# Sensors.net
KiCad netlist of a schematic drawn in Altium Designer
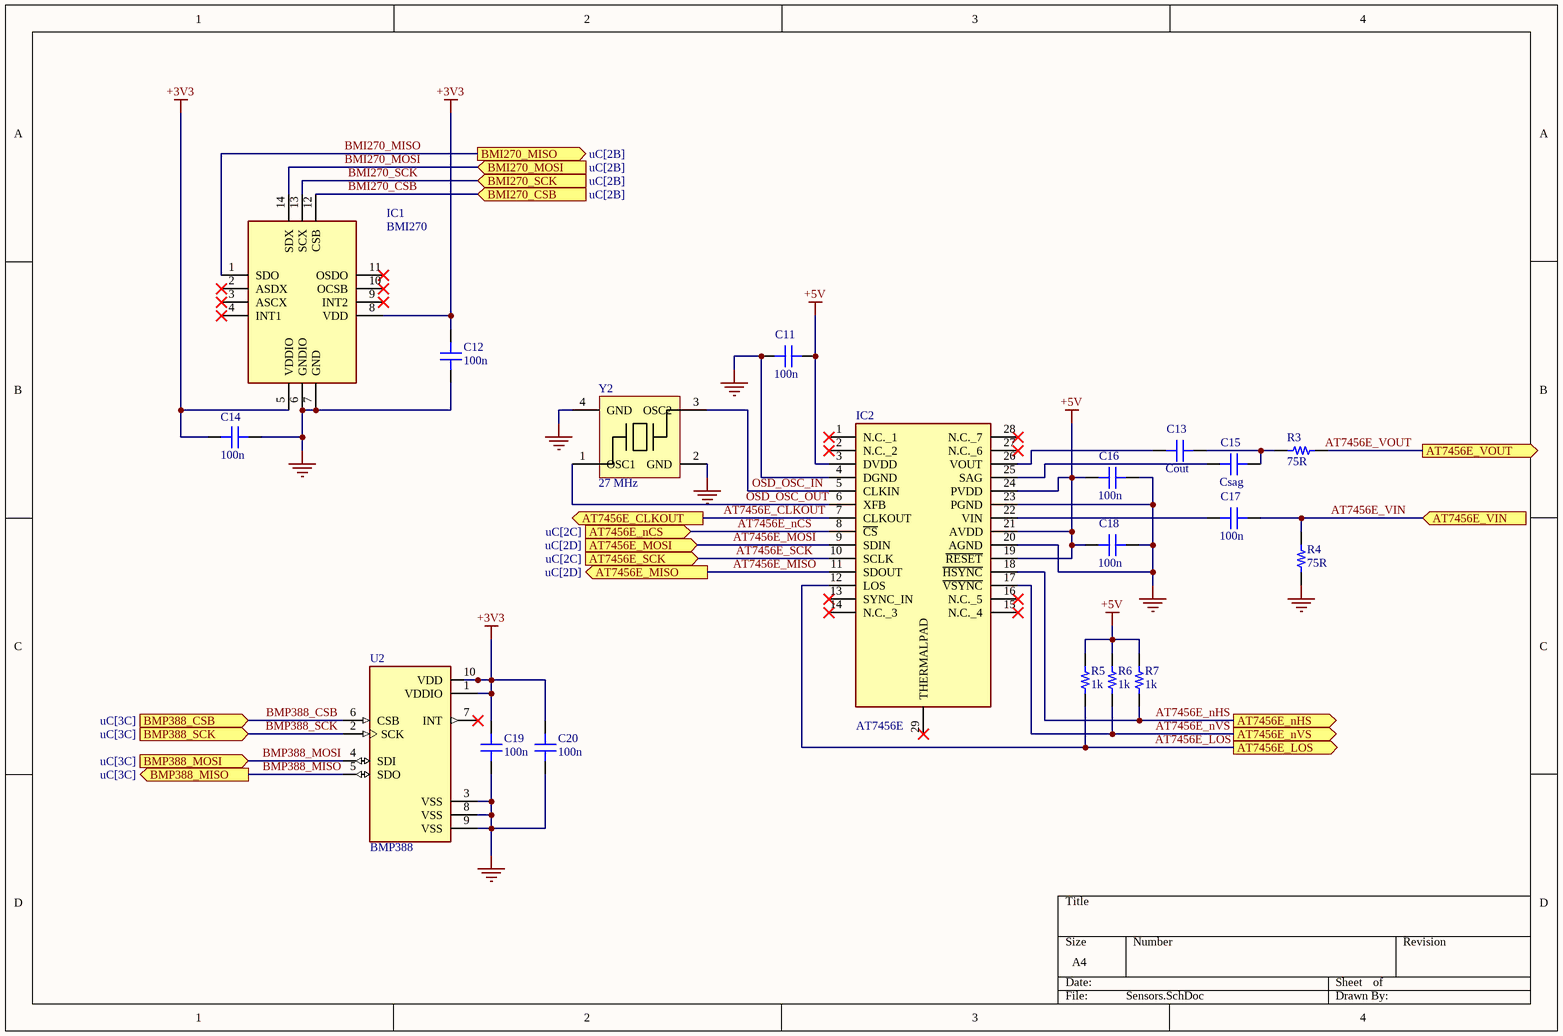
[diagram p0: Sensors.SchDoc]

(export (version "E")
  (design (tool "Eeschema 10.0.6"))
  (components
    (comp (ref "C11")
      (value "0.1 µF")
      (footprint "CAP 0603_1608")
      (description "CAP CER 0.1UF 50V X7R 0603")
      (fields
        (field (name "PART NUMBER") "CL10B104KB8NNNC")
        (field (name "CAPACITANCE") "100n")
        (field (name "MANUFACTURER") "Samsung Electro-Mechanics")
      )
      (libsource (lib "Celestial Altium Library - altium_library") (part "Capacitor"))
    )
    (comp (ref "C12")
      (value "0.1 µF")
      (footprint "CAP 0603_1608")
      (description "CAP CER 0.1UF 50V X7R 0603")
      (fields
        (field (name "PART NUMBER") "CL10B104KB8NNNC")
        (field (name "CAPACITANCE") "100n")
        (field (name "MANUFACTURER") "Samsung Electro-Mechanics")
      )
      (libsource (lib "Celestial Altium Library - altium_library") (part "Capacitor"))
    )
    (comp (ref "C13")
      (value "0.1 µF")
      (footprint "CAP 0603_1608")
      (description "CAP CER 0.1UF 50V X7R 0603")
      (fields
        (field (name "PART NUMBER") "CL10B104KB8NNNC")
        (field (name "CAPACITANCE") "Cout")
        (field (name "MANUFACTURER") "Samsung Electro-Mechanics")
      )
      (libsource (lib "Celestial Altium Library - altium_library") (part "Capacitor"))
    )
    (comp (ref "C14")
      (value "0.1 µF")
      (footprint "CAP 0603_1608")
      (description "CAP CER 0.1UF 50V X7R 0603")
      (fields
        (field (name "PART NUMBER") "CL10B104KB8NNNC")
        (field (name "CAPACITANCE") "100n")
        (field (name "MANUFACTURER") "Samsung Electro-Mechanics")
      )
      (libsource (lib "Celestial Altium Library - altium_library") (part "Capacitor"))
    )
    (comp (ref "C15")
      (value "0.1 µF")
      (footprint "CAP 0603_1608")
      (description "CAP CER 0.1UF 50V X7R 0603")
      (fields
        (field (name "PART NUMBER") "CL10B104KB8NNNC")
        (field (name "CAPACITANCE") "Csag")
        (field (name "MANUFACTURER") "Samsung Electro-Mechanics")
      )
      (libsource (lib "Celestial Altium Library - altium_library") (part "Capacitor"))
    )
    (comp (ref "C16")
      (value "0.1 µF")
      (footprint "CAP 0603_1608")
      (description "CAP CER 0.1UF 50V X7R 0603")
      (fields
        (field (name "PART NUMBER") "CL10B104KB8NNNC")
        (field (name "CAPACITANCE") "100n")
        (field (name "MANUFACTURER") "Samsung Electro-Mechanics")
      )
      (libsource (lib "Celestial Altium Library - altium_library") (part "Capacitor"))
    )
    (comp (ref "C17")
      (value "0.1 µF")
      (footprint "CAP 0603_1608")
      (description "CAP CER 0.1UF 50V X7R 0603")
      (fields
        (field (name "PART NUMBER") "CL10B104KB8NNNC")
        (field (name "CAPACITANCE") "100n")
        (field (name "MANUFACTURER") "Samsung Electro-Mechanics")
      )
      (libsource (lib "Celestial Altium Library - altium_library") (part "Capacitor"))
    )
    (comp (ref "C18")
      (value "0.1 µF")
      (footprint "CAP 0603_1608")
      (description "CAP CER 0.1UF 50V X7R 0603")
      (fields
        (field (name "PART NUMBER") "CL10B104KB8NNNC")
        (field (name "CAPACITANCE") "100n")
        (field (name "MANUFACTURER") "Samsung Electro-Mechanics")
      )
      (libsource (lib "Celestial Altium Library - altium_library") (part "Capacitor"))
    )
    (comp (ref "C19")
      (value "0.1 µF")
      (footprint "CAP 0603_1608")
      (description "CAP CER 0.1UF 50V X7R 0603")
      (fields
        (field (name "PART NUMBER") "CL10B104KB8NNNC")
        (field (name "CAPACITANCE") "100n")
        (field (name "MANUFACTURER") "Samsung Electro-Mechanics")
      )
      (libsource (lib "Celestial Altium Library - altium_library") (part "Capacitor"))
    )
    (comp (ref "C20")
      (value "0.1 µF")
      (footprint "CAP 0603_1608")
      (description "CAP CER 0.1UF 50V X7R 0603")
      (fields
        (field (name "PART NUMBER") "CL10B104KB8NNNC")
        (field (name "CAPACITANCE") "100n")
        (field (name "MANUFACTURER") "Samsung Electro-Mechanics")
      )
      (libsource (lib "Celestial Altium Library - altium_library") (part "Capacitor"))
    )
    (comp (ref "IC1")
      (value "BMI270")
      (footprint "SamacSys:BMI270")
      (description "Integrated Circuit")
      (fields (field (name "MOUSER PART NUMBER") "262-BMI270"))
      (libsource (lib "*") (part "BMI270"))
    )
    (comp (ref "IC2")
      (value "AT7456E")
      (footprint "SamacSys:SOP65P640X120-29N")
      (description "Integrated Circuit")
      (libsource (lib "SamacSys") (part "AT7456E"))
    )
    (comp (ref "R3")
      (value "75R")
      (footprint "YAGEO RES 0603_1608")
      (description "RES 75 OHM 1% 1/10W 0603")
      (fields (field (name "PART NUMBER") "RC0603FR-0775RL") (field (name "MANUFACTURER") "Yageo"))
      (libsource (lib "Celestial Altium Library - altium_library") (part "Resistor"))
    )
    (comp (ref "R4")
      (value "75R")
      (footprint "YAGEO RES 0603_1608")
      (description "RES 75 OHM 1% 1/10W 0603")
      (fields (field (name "PART NUMBER") "RC0603FR-0775RL") (field (name "MANUFACTURER") "Yageo"))
      (libsource (lib "Celestial Altium Library - altium_library") (part "Resistor"))
    )
    (comp (ref "R5")
      (value "1k")
      (footprint "YAGEO RES 0603_1608")
      (description "RES 1K OHM 1% 1/10W 0603")
      (fields (field (name "PART NUMBER") "RC0603FR-071KL") (field (name "MANUFACTURER") "Yageo"))
      (libsource (lib "Celestial Altium Library - altium_library") (part "Resistor"))
    )
    (comp (ref "R6")
      (value "1k")
      (footprint "YAGEO RES 0603_1608")
      (description "RES 1K OHM 1% 1/10W 0603")
      (fields (field (name "PART NUMBER") "RC0603FR-071KL") (field (name "MANUFACTURER") "Yageo"))
      (libsource (lib "Celestial Altium Library - altium_library") (part "Resistor"))
    )
    (comp (ref "R7")
      (value "1k")
      (footprint "YAGEO RES 0603_1608")
      (description "RES 1K OHM 1% 1/10W 0603")
      (fields (field (name "PART NUMBER") "RC0603FR-071KL") (field (name "MANUFACTURER") "Yageo"))
      (libsource (lib "Celestial Altium Library - altium_library") (part "Resistor"))
    )
    (comp (ref "U2")
      (value "BMP388")
      (footprint "PQFN50P200X200X80-10N")
      (description "P-Sensor SPI I2C 1, 25 Bar SMD")
      (libsource (lib "BMP388") (part "BMP388"))
    )
    (comp (ref "Y2")
      (value "27 MHz")
      (footprint "X322527MSB4SI")
      (libsource (lib "SamacSys") (part "X322527MSB4SI"))
    )
  )
  (nets
    (net (code "1") (name "+3V3") (class "Default")
      (node (ref "C12") (pin "1") (pinfunction "1_1") (pintype "passive"))
      (node (ref "C14") (pin "2") (pinfunction "2_2") (pintype "passive"))
      (node (ref "C19") (pin "1") (pinfunction "1_1") (pintype "passive"))
      (node (ref "C20") (pin "1") (pinfunction "1_1") (pintype "passive"))
      (node (ref "IC1") (pin "5") (pinfunction "VDDIO_5") (pintype "passive"))
      (node (ref "IC1") (pin "8") (pinfunction "VDD_8") (pintype "passive"))
      (node (ref "U2") (pin "1") (pinfunction "VDDIO_1") (pintype "power_in"))
      (node (ref "U2") (pin "10") (pinfunction "VDD_10") (pintype "power_in"))
    )
    (net (code "2") (name "+5V") (class "Default")
      (node (ref "C11") (pin "2") (pinfunction "2_2") (pintype "passive"))
      (node (ref "C16") (pin "1") (pinfunction "1_1") (pintype "passive"))
      (node (ref "C18") (pin "1") (pinfunction "1_1") (pintype "passive"))
      (node (ref "IC2") (pin "19") (pinfunction "~{RESET}_19") (pintype "passive"))
      (node (ref "IC2") (pin "21") (pinfunction "AVDD_21") (pintype "passive"))
      (node (ref "IC2") (pin "24") (pinfunction "PVDD_24") (pintype "passive"))
      (node (ref "IC2") (pin "3") (pinfunction "DVDD_3") (pintype "passive"))
      (node (ref "R5") (pin "2") (pinfunction "2_2") (pintype "passive"))
      (node (ref "R6") (pin "2") (pinfunction "2_2") (pintype "passive"))
      (node (ref "R7") (pin "2") (pinfunction "2_2") (pintype "passive"))
    )
    (net (code "3") (name "/AT7456E_CLKOUT") (class "Default")
      (node (ref "IC2") (pin "7") (pinfunction "CLKOUT_7") (pintype "passive"))
    )
    (net (code "4") (name "/AT7456E_LOS") (class "Default")
      (node (ref "IC2") (pin "12") (pinfunction "LOS_12") (pintype "passive"))
      (node (ref "R5") (pin "1") (pinfunction "1_1") (pintype "passive"))
    )
    (net (code "5") (name "/AT7456E_MISO") (class "Default")
      (node (ref "IC2") (pin "11") (pinfunction "SDOUT_11") (pintype "passive"))
    )
    (net (code "6") (name "/AT7456E_MOSI") (class "Default")
      (node (ref "IC2") (pin "9") (pinfunction "SDIN_9") (pintype "passive"))
    )
    (net (code "7") (name "/AT7456E_SCK") (class "Default")
      (node (ref "IC2") (pin "10") (pinfunction "SCLK_10") (pintype "passive"))
    )
    (net (code "8") (name "/AT7456E_VIN") (class "Default")
      (node (ref "C17") (pin "2") (pinfunction "2_2") (pintype "passive"))
      (node (ref "R4") (pin "1") (pinfunction "1_1") (pintype "passive"))
    )
    (net (code "9") (name "/AT7456E_VOUT") (class "Default")
      (node (ref "R3") (pin "1") (pinfunction "1_1") (pintype "passive"))
    )
    (net (code "10") (name "/AT7456E_nCS") (class "Default")
      (node (ref "IC2") (pin "8") (pinfunction "~{CS}_8") (pintype "passive"))
    )
    (net (code "11") (name "/AT7456E_nHS") (class "Default")
      (node (ref "IC2") (pin "18") (pinfunction "~{HSYNC}_18") (pintype "passive"))
      (node (ref "R7") (pin "1") (pinfunction "1_1") (pintype "passive"))
    )
    (net (code "12") (name "/AT7456E_nVS") (class "Default")
      (node (ref "IC2") (pin "17") (pinfunction "~{VSYNC}_17") (pintype "passive"))
      (node (ref "R6") (pin "1") (pinfunction "1_1") (pintype "passive"))
    )
    (net (code "13") (name "/BMI270_CSB") (class "Default")
      (node (ref "IC1") (pin "12") (pinfunction "CSB_12") (pintype "passive"))
    )
    (net (code "14") (name "/BMI270_MISO") (class "Default")
      (node (ref "IC1") (pin "1") (pinfunction "SDO_1") (pintype "passive"))
    )
    (net (code "15") (name "/BMI270_MOSI") (class "Default")
      (node (ref "IC1") (pin "14") (pinfunction "SDX_14") (pintype "passive"))
    )
    (net (code "16") (name "/BMI270_SCK") (class "Default")
      (node (ref "IC1") (pin "13") (pinfunction "SCX_13") (pintype "passive"))
    )
    (net (code "17") (name "/BMP388_CSB") (class "Default")
      (node (ref "U2") (pin "6") (pinfunction "CSB_6") (pintype "input"))
    )
    (net (code "18") (name "/BMP388_MISO") (class "Default")
      (node (ref "U2") (pin "5") (pinfunction "SDO_5") (pintype "bidirectional"))
    )
    (net (code "19") (name "/BMP388_MOSI") (class "Default")
      (node (ref "U2") (pin "4") (pinfunction "SDI_4") (pintype "bidirectional"))
    )
    (net (code "20") (name "/BMP388_SCK") (class "Default")
      (node (ref "U2") (pin "2") (pinfunction "SCK_2") (pintype "input"))
    )
    (net (code "21") (name "/OSD_OSC_IN") (class "Default")
      (node (ref "IC2") (pin "5") (pinfunction "CLKIN_5") (pintype "passive"))
      (node (ref "Y2") (pin "3") (pinfunction "OSC2_3") (pintype "passive"))
    )
    (net (code "22") (name "/OSD_OSC_OUT") (class "Default")
      (node (ref "IC2") (pin "6") (pinfunction "XFB_6") (pintype "passive"))
      (node (ref "Y2") (pin "1") (pinfunction "OSC1_1") (pintype "passive"))
    )
    (net (code "23") (name "GND") (class "Default")
      (node (ref "C11") (pin "1") (pinfunction "1_1") (pintype "passive"))
      (node (ref "C12") (pin "2") (pinfunction "2_2") (pintype "passive"))
      (node (ref "C14") (pin "1") (pinfunction "1_1") (pintype "passive"))
      (node (ref "C16") (pin "2") (pinfunction "2_2") (pintype "passive"))
      (node (ref "C18") (pin "2") (pinfunction "2_2") (pintype "passive"))
      (node (ref "C19") (pin "2") (pinfunction "2_2") (pintype "passive"))
      (node (ref "C20") (pin "2") (pinfunction "2_2") (pintype "passive"))
      (node (ref "IC1") (pin "6") (pinfunction "GNDIO_6") (pintype "passive"))
      (node (ref "IC1") (pin "7") (pinfunction "GND_7") (pintype "passive"))
      (node (ref "IC2") (pin "20") (pinfunction "AGND_20") (pintype "passive"))
      (node (ref "IC2") (pin "23") (pinfunction "PGND_23") (pintype "passive"))
      (node (ref "IC2") (pin "4") (pinfunction "DGND_4") (pintype "passive"))
      (node (ref "R4") (pin "2") (pinfunction "2_2") (pintype "passive"))
      (node (ref "U2") (pin "3") (pinfunction "VSS_3") (pintype "power_in"))
      (node (ref "U2") (pin "8") (pinfunction "VSS_8") (pintype "power_in"))
      (node (ref "U2") (pin "9") (pinfunction "VSS_9") (pintype "power_in"))
      (node (ref "Y2") (pin "2") (pinfunction "GND_2") (pintype "passive"))
      (node (ref "Y2") (pin "4") (pinfunction "GND_4") (pintype "passive"))
    )
    (net (code "24") (name "Net-(C13-Pad2)") (class "Default")
      (node (ref "C13") (pin "2") (pinfunction "2_2") (pintype "passive"))
      (node (ref "C15") (pin "2") (pinfunction "2_2") (pintype "passive"))
      (node (ref "R3") (pin "2") (pinfunction "2_2") (pintype "passive"))
    )
    (net (code "25") (name "Net-(IC2-SAG)") (class "Default")
      (node (ref "C15") (pin "1") (pinfunction "1_1") (pintype "passive"))
      (node (ref "IC2") (pin "25") (pinfunction "SAG_25") (pintype "passive"))
    )
    (net (code "26") (name "Net-(IC2-VIN)") (class "Default")
      (node (ref "C17") (pin "1") (pinfunction "1_1") (pintype "passive"))
      (node (ref "IC2") (pin "22") (pinfunction "VIN_22") (pintype "passive"))
    )
    (net (code "27") (name "Net-(IC2-VOUT)") (class "Default")
      (node (ref "C13") (pin "1") (pinfunction "1_1") (pintype "passive"))
      (node (ref "IC2") (pin "26") (pinfunction "VOUT_26") (pintype "passive"))
    )
    (net (code "28") (name "unconnected-(IC1-ASCX-Pad3)") (class "Default")
      (node (ref "IC1") (pin "3") (pinfunction "ASCX_3") (pintype "passive+no_connect"))
    )
    (net (code "29") (name "unconnected-(IC1-ASDX-Pad2)") (class "Default")
      (node (ref "IC1") (pin "2") (pinfunction "ASDX_2") (pintype "passive+no_connect"))
    )
    (net (code "30") (name "unconnected-(IC1-INT1-Pad4)") (class "Default")
      (node (ref "IC1") (pin "4") (pinfunction "INT1_4") (pintype "passive+no_connect"))
    )
    (net (code "31") (name "unconnected-(IC1-INT2-Pad9)") (class "Default")
      (node (ref "IC1") (pin "9") (pinfunction "INT2_9") (pintype "passive+no_connect"))
    )
    (net (code "32") (name "unconnected-(IC1-OCSB-Pad10)") (class "Default")
      (node (ref "IC1") (pin "10") (pinfunction "OCSB_10") (pintype "passive+no_connect"))
    )
    (net (code "33") (name "unconnected-(IC1-OSDO-Pad11)") (class "Default")
      (node (ref "IC1") (pin "11") (pinfunction "OSDO_11") (pintype "passive+no_connect"))
    )
    (net (code "34") (name "unconnected-(IC2-N.C._1-Pad1)") (class "Default")
      (node (ref "IC2") (pin "1") (pinfunction "N.C._1_1") (pintype "passive+no_connect"))
    )
    (net (code "35") (name "unconnected-(IC2-N.C._2-Pad2)") (class "Default")
      (node (ref "IC2") (pin "2") (pinfunction "N.C._2_2") (pintype "passive+no_connect"))
    )
    (net (code "36") (name "unconnected-(IC2-N.C._3-Pad14)") (class "Default")
      (node (ref "IC2") (pin "14") (pinfunction "N.C._3_14") (pintype "passive+no_connect"))
    )
    (net (code "37") (name "unconnected-(IC2-N.C._4-Pad15)") (class "Default")
      (node (ref "IC2") (pin "15") (pinfunction "N.C._4_15") (pintype "passive+no_connect"))
    )
    (net (code "38") (name "unconnected-(IC2-N.C._5-Pad16)") (class "Default")
      (node (ref "IC2") (pin "16") (pinfunction "N.C._5_16") (pintype "passive+no_connect"))
    )
    (net (code "39") (name "unconnected-(IC2-N.C._6-Pad27)") (class "Default")
      (node (ref "IC2") (pin "27") (pinfunction "N.C._6_27") (pintype "passive+no_connect"))
    )
    (net (code "40") (name "unconnected-(IC2-N.C._7-Pad28)") (class "Default")
      (node (ref "IC2") (pin "28") (pinfunction "N.C._7_28") (pintype "passive+no_connect"))
    )
    (net (code "41") (name "unconnected-(IC2-SYNC_IN-Pad13)") (class "Default")
      (node (ref "IC2") (pin "13") (pinfunction "SYNC_IN_13") (pintype "passive+no_connect"))
    )
    (net (code "42") (name "unconnected-(IC2-THERMALPAD-Pad29)") (class "Default")
      (node (ref "IC2") (pin "29") (pinfunction "THERMALPAD_29") (pintype "passive+no_connect"))
    )
    (net (code "43") (name "unconnected-(U2-INT-Pad7)") (class "Default")
      (node (ref "U2") (pin "7") (pinfunction "INT_7") (pintype "output+no_connect"))
    )
  )
)
